# HeaderA.net
KiCad netlist of a schematic drawn in Altium Designer
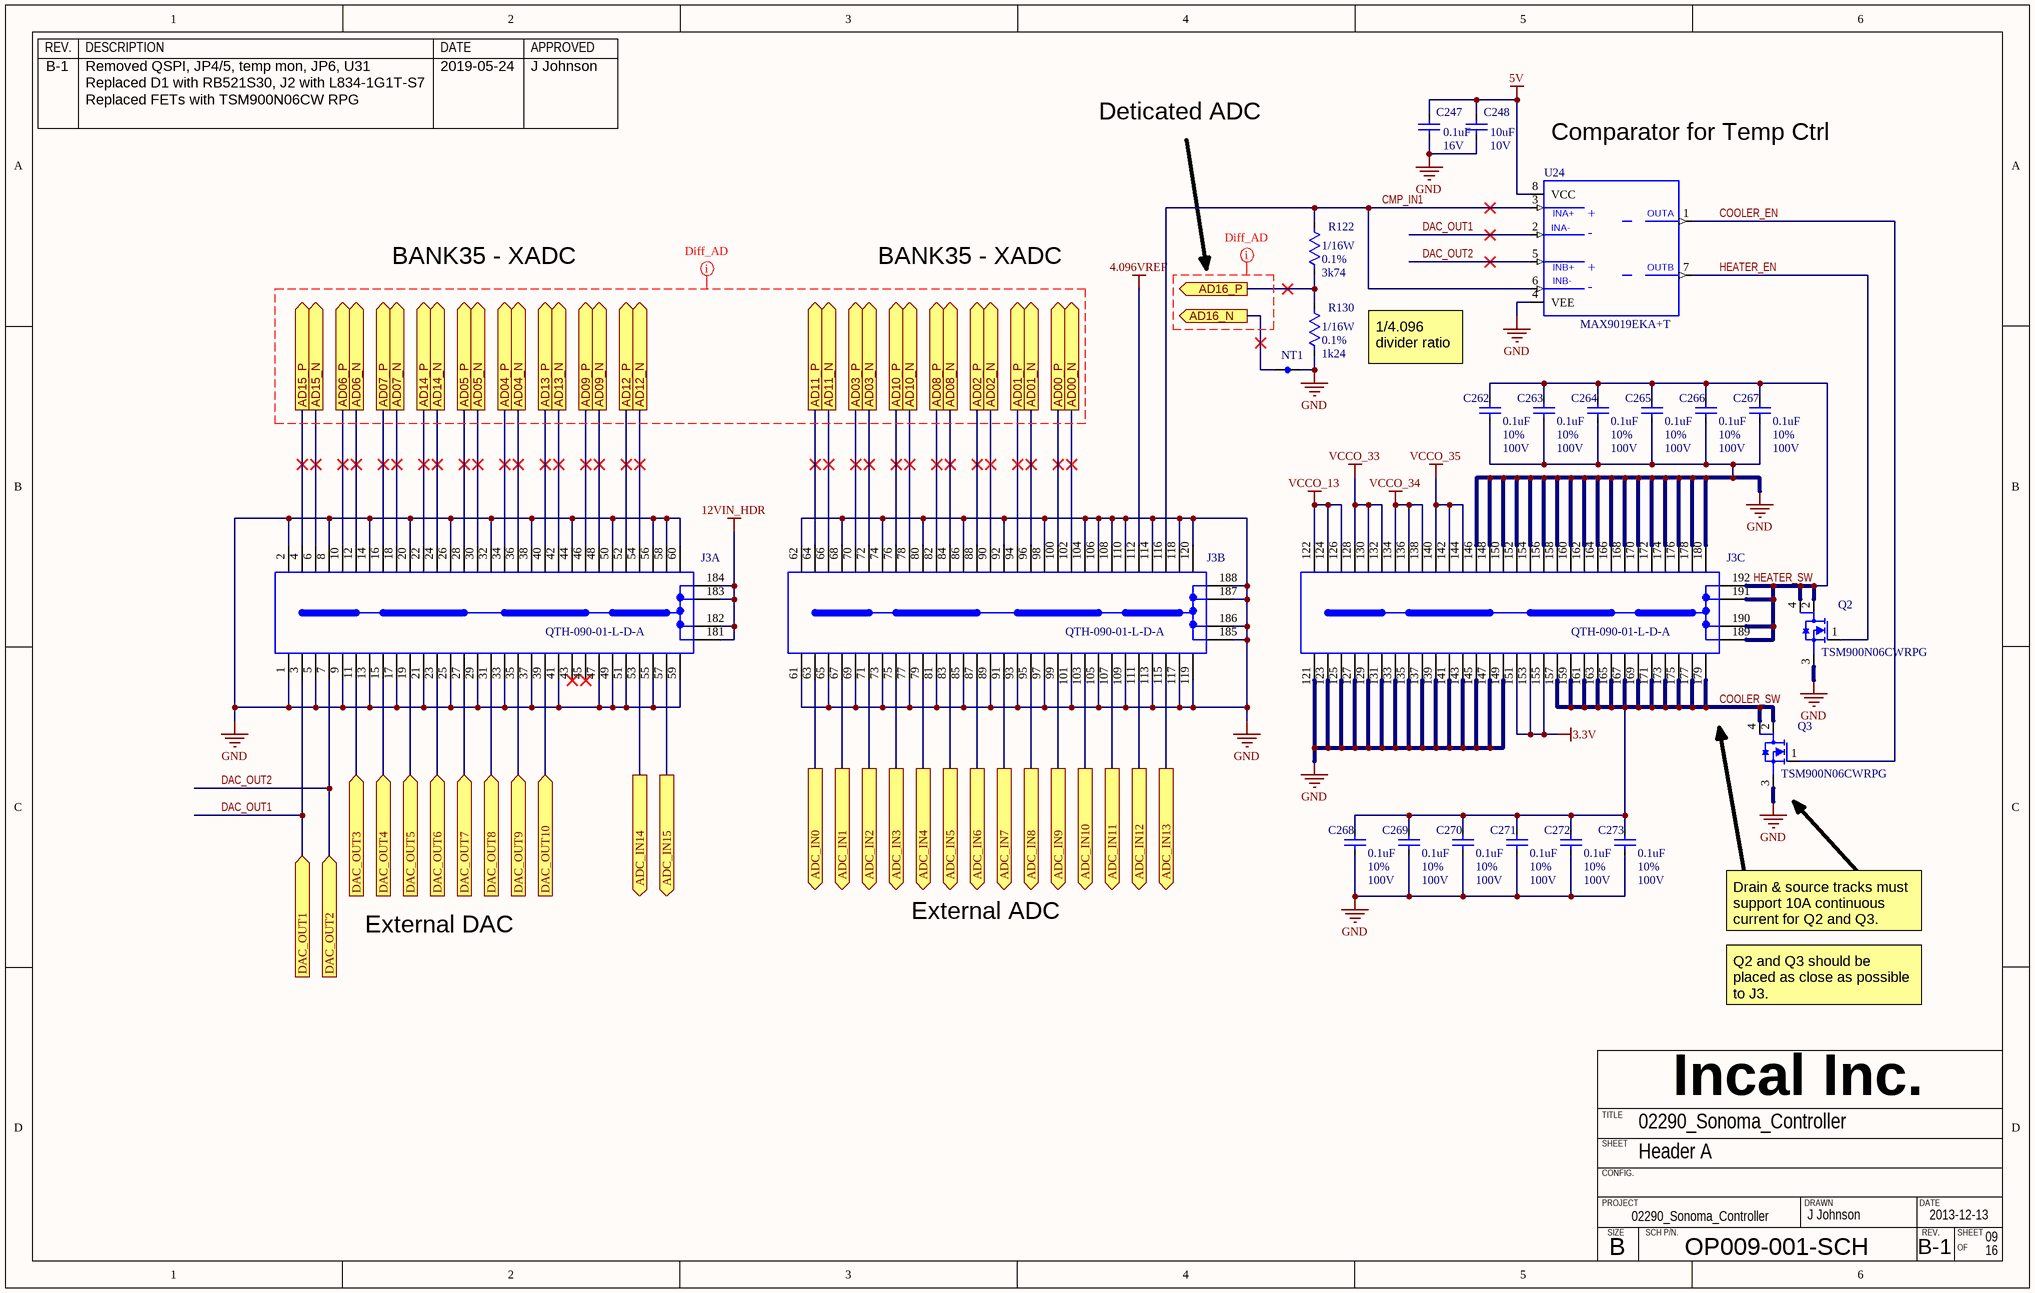
[diagram p0: HeaderA.SchDoc]

(export (version "E")
  (design (tool "Eeschema 10.0.6"))
  (components
    (comp (ref "C247")
      (value "0.1uF")
      (footprint "CAPC1005X33N")
      (description "Capacitor ceramic, X7R, 0.1uF, 16V, 10%, -55 to +125 C, EIA0402")
      (fields
        (field (name "TOLERANCE") "10%")
        (field (name "VOLTAGE") "16V")
        (field (name "Comment") "CAPACITOR_NP_TYPE1")
      )
      (libsource (lib "parts") (part "CAPACITOR_NP_TYPE1"))
    )
    (comp (ref "C248")
      (value "10uF")
      (footprint "CAPC1608X38N")
      (description "Capacitor ceramic, X5R, 10uF, 10V, 10%, -55 to +85 C, EIA0603")
      (fields
        (field (name "TOLERANCE") "10%")
        (field (name "VOLTAGE") "10V")
        (field (name "Comment") "CAPACITOR_NP_TYPE1")
      )
      (libsource (lib "parts") (part "CAPACITOR_NP_TYPE1"))
    )
    (comp (ref "C262")
      (value "0.1uF")
      (footprint "CAPC1608X38N")
      (description "Capacitor ceramic, X7R, 0.1uF, 100V, 10%, -55 to +125 C, EIA0603")
      (fields
        (field (name "TOLERANCE") "10%")
        (field (name "VOLTAGE") "100V")
        (field (name "Comment") "CAPACITOR_NP_TYPE1")
      )
      (libsource (lib "parts") (part "CAPACITOR_NP_TYPE1"))
    )
    (comp (ref "C263")
      (value "0.1uF")
      (footprint "CAPC1608X38N")
      (description "Capacitor ceramic, X7R, 0.1uF, 100V, 10%, -55 to +125 C, EIA0603")
      (fields
        (field (name "TOLERANCE") "10%")
        (field (name "VOLTAGE") "100V")
        (field (name "Comment") "CAPACITOR_NP_TYPE1")
      )
      (libsource (lib "parts") (part "CAPACITOR_NP_TYPE1"))
    )
    (comp (ref "C264")
      (value "0.1uF")
      (footprint "CAPC1608X38N")
      (description "Capacitor ceramic, X7R, 0.1uF, 100V, 10%, -55 to +125 C, EIA0603")
      (fields
        (field (name "TOLERANCE") "10%")
        (field (name "VOLTAGE") "100V")
        (field (name "Comment") "CAPACITOR_NP_TYPE1")
      )
      (libsource (lib "parts") (part "CAPACITOR_NP_TYPE1"))
    )
    (comp (ref "C265")
      (value "0.1uF")
      (footprint "CAPC1608X38N")
      (description "Capacitor ceramic, X7R, 0.1uF, 100V, 10%, -55 to +125 C, EIA0603")
      (fields
        (field (name "TOLERANCE") "10%")
        (field (name "VOLTAGE") "100V")
        (field (name "Comment") "CAPACITOR_NP_TYPE1")
      )
      (libsource (lib "parts") (part "CAPACITOR_NP_TYPE1"))
    )
    (comp (ref "C266")
      (value "0.1uF")
      (footprint "CAPC1608X38N")
      (description "Capacitor ceramic, X7R, 0.1uF, 100V, 10%, -55 to +125 C, EIA0603")
      (fields
        (field (name "TOLERANCE") "10%")
        (field (name "VOLTAGE") "100V")
        (field (name "Comment") "CAPACITOR_NP_TYPE1")
      )
      (libsource (lib "parts") (part "CAPACITOR_NP_TYPE1"))
    )
    (comp (ref "C267")
      (value "0.1uF")
      (footprint "CAPC1608X38N")
      (description "Capacitor ceramic, X7R, 0.1uF, 100V, 10%, -55 to +125 C, EIA0603")
      (fields
        (field (name "TOLERANCE") "10%")
        (field (name "VOLTAGE") "100V")
        (field (name "Comment") "CAPACITOR_NP_TYPE1")
      )
      (libsource (lib "parts") (part "CAPACITOR_NP_TYPE1"))
    )
    (comp (ref "C268")
      (value "0.1uF")
      (footprint "CAPC1608X38N")
      (description "Capacitor ceramic, X7R, 0.1uF, 100V, 10%, -55 to +125 C, EIA0603")
      (fields
        (field (name "TOLERANCE") "10%")
        (field (name "VOLTAGE") "100V")
        (field (name "Comment") "CAPACITOR_NP_TYPE1")
      )
      (libsource (lib "parts") (part "CAPACITOR_NP_TYPE1"))
    )
    (comp (ref "C269")
      (value "0.1uF")
      (footprint "CAPC1608X38N")
      (description "Capacitor ceramic, X7R, 0.1uF, 100V, 10%, -55 to +125 C, EIA0603")
      (fields
        (field (name "TOLERANCE") "10%")
        (field (name "VOLTAGE") "100V")
        (field (name "Comment") "CAPACITOR_NP_TYPE1")
      )
      (libsource (lib "parts") (part "CAPACITOR_NP_TYPE1"))
    )
    (comp (ref "C270")
      (value "0.1uF")
      (footprint "CAPC1608X38N")
      (description "Capacitor ceramic, X7R, 0.1uF, 100V, 10%, -55 to +125 C, EIA0603")
      (fields
        (field (name "TOLERANCE") "10%")
        (field (name "VOLTAGE") "100V")
        (field (name "Comment") "CAPACITOR_NP_TYPE1")
      )
      (libsource (lib "parts") (part "CAPACITOR_NP_TYPE1"))
    )
    (comp (ref "C271")
      (value "0.1uF")
      (footprint "CAPC1608X38N")
      (description "Capacitor ceramic, X7R, 0.1uF, 100V, 10%, -55 to +125 C, EIA0603")
      (fields
        (field (name "TOLERANCE") "10%")
        (field (name "VOLTAGE") "100V")
        (field (name "Comment") "CAPACITOR_NP_TYPE1")
      )
      (libsource (lib "parts") (part "CAPACITOR_NP_TYPE1"))
    )
    (comp (ref "C272")
      (value "0.1uF")
      (footprint "CAPC1608X38N")
      (description "Capacitor ceramic, X7R, 0.1uF, 100V, 10%, -55 to +125 C, EIA0603")
      (fields
        (field (name "TOLERANCE") "10%")
        (field (name "VOLTAGE") "100V")
        (field (name "Comment") "CAPACITOR_NP_TYPE1")
      )
      (libsource (lib "parts") (part "CAPACITOR_NP_TYPE1"))
    )
    (comp (ref "C273")
      (value "0.1uF")
      (footprint "CAPC1608X38N")
      (description "Capacitor ceramic, X7R, 0.1uF, 100V, 10%, -55 to +125 C, EIA0603")
      (fields
        (field (name "TOLERANCE") "10%")
        (field (name "VOLTAGE") "100V")
        (field (name "Comment") "CAPACITOR_NP_TYPE1")
      )
      (libsource (lib "parts") (part "CAPACITOR_NP_TYPE1"))
    )
    (comp (ref "J3")
      (value "QTH-090-01-L-D-A")
      (footprint "QTH-090-01-L-D-A")
      (description "Connector Header HS .5mm 180 pin DL AU")
      (libsource (lib "parts") (part "QTH-090-01-L-D-A"))
    )
    (comp (ref "NT1")
      (value "NET_TIE_1X1")
      (footprint "NET_TIE_1X1")
      (description "Net Tie 1 to 1")
      (libsource (lib "parts") (part "NET_TIE_1X1"))
    )
    (comp (ref "Q2")
      (value "TSM900N06CWRPG")
      (footprint "SOT230P700X180-4N")
      (description "Transistor MOSFET, N-Channel, 60V, 11A, 25W, SOT-223")
      (fields (field (name "POWER") "25W") (field (name "VOLTAGE") "60V"))
      (libsource (lib "parts") (part "TRANS_MOSFET_N-CH_TYPE4"))
    )
    (comp (ref "Q3")
      (value "TSM900N06CWRPG")
      (footprint "SOT230P700X180-4N")
      (description "Transistor MOSFET, N-Channel, 60V, 11A, 25W, SOT-223")
      (fields (field (name "POWER") "25W") (field (name "VOLTAGE") "60V"))
      (libsource (lib "parts") (part "TRANS_MOSFET_N-CH_TYPE4"))
    )
    (comp (ref "R122")
      (value "3k74")
      (footprint "RESC1005X33N")
      (description "Resistor, 3k74, 1/16W, 0.1%, -50 to +155 C, EIA0402, EIA(M)1005")
      (fields (field (name "VOLTAGE") "50V") (field (name "POWER") "1/16W") (field (name "TOLERANCE") "0.1%"))
      (libsource (lib "parts") (part "RESISTOR_TYPE1"))
    )
    (comp (ref "R130")
      (value "1k24")
      (footprint "RESC1005X33N")
      (description "Resistor, 1k24, 1/16W, 0.1%, -50 to +155 C, EIA0402, EIA(M)1005")
      (fields (field (name "VOLTAGE") "50V") (field (name "POWER") "1/16W") (field (name "TOLERANCE") "0.1%"))
      (libsource (lib "parts") (part "RESISTOR_TYPE1"))
    )
    (comp (ref "U24")
      (value "MAX9019EKA+T")
      (footprint "SOT65P280X145-8AN")
      (description "Comparator, Dual, Push-pull, 1.8V to 5.5V, 50mA, -40 to +85 C, , SOT-23-8")
      (fields (field (name "POWER") "Pow") (field (name "VOLTAGE") "1.8V to 5.5V"))
      (libsource (lib "parts") (part "MAX9019"))
    )
  )
  (nets
    (net (code "1") (name "/AD00_N") (class "Default")
      (node (ref "J3") (pin "102") (pinfunction "102_102") (pintype "passive"))
    )
    (net (code "2") (name "/AD00_P") (class "Default")
      (node (ref "J3") (pin "100") (pinfunction "100_100") (pintype "passive"))
    )
    (net (code "3") (name "/AD01_N") (class "Default")
      (node (ref "J3") (pin "96") (pinfunction "96_96") (pintype "passive"))
    )
    (net (code "4") (name "/AD01_P") (class "Default")
      (node (ref "J3") (pin "94") (pinfunction "94_94") (pintype "passive"))
    )
    (net (code "5") (name "/AD02_N") (class "Default")
      (node (ref "J3") (pin "90") (pinfunction "90_90") (pintype "passive"))
    )
    (net (code "6") (name "/AD02_P") (class "Default")
      (node (ref "J3") (pin "88") (pinfunction "88_88") (pintype "passive"))
    )
    (net (code "7") (name "/AD03_N") (class "Default")
      (node (ref "J3") (pin "72") (pinfunction "72_72") (pintype "passive"))
    )
    (net (code "8") (name "/AD03_P") (class "Default")
      (node (ref "J3") (pin "70") (pinfunction "70_70") (pintype "passive"))
    )
    (net (code "9") (name "/AD04_N") (class "Default")
      (node (ref "J3") (pin "36") (pinfunction "36_36") (pintype "passive"))
    )
    (net (code "10") (name "/AD04_P") (class "Default")
      (node (ref "J3") (pin "34") (pinfunction "34_34") (pintype "passive"))
    )
    (net (code "11") (name "/AD05_N") (class "Default")
      (node (ref "J3") (pin "30") (pinfunction "30_30") (pintype "passive"))
    )
    (net (code "12") (name "/AD05_P") (class "Default")
      (node (ref "J3") (pin "28") (pinfunction "28_28") (pintype "passive"))
    )
    (net (code "13") (name "/AD06_N") (class "Default")
      (node (ref "J3") (pin "12") (pinfunction "12_12") (pintype "passive"))
    )
    (net (code "14") (name "/AD06_P") (class "Default")
      (node (ref "J3") (pin "10") (pinfunction "10_10") (pintype "passive"))
    )
    (net (code "15") (name "/AD07_N") (class "Default")
      (node (ref "J3") (pin "18") (pinfunction "18_18") (pintype "passive"))
    )
    (net (code "16") (name "/AD07_P") (class "Default")
      (node (ref "J3") (pin "16") (pinfunction "16_16") (pintype "passive"))
    )
    (net (code "17") (name "/AD08_N") (class "Default")
      (node (ref "J3") (pin "84") (pinfunction "84_84") (pintype "passive"))
    )
    (net (code "18") (name "/AD08_P") (class "Default")
      (node (ref "J3") (pin "82") (pinfunction "82_82") (pintype "passive"))
    )
    (net (code "19") (name "/AD09_N") (class "Default")
      (node (ref "J3") (pin "48") (pinfunction "48_48") (pintype "passive"))
    )
    (net (code "20") (name "/AD09_P") (class "Default")
      (node (ref "J3") (pin "46") (pinfunction "46_46") (pintype "passive"))
    )
    (net (code "21") (name "/AD10_N") (class "Default")
      (node (ref "J3") (pin "78") (pinfunction "78_78") (pintype "passive"))
    )
    (net (code "22") (name "/AD10_P") (class "Default")
      (node (ref "J3") (pin "76") (pinfunction "76_76") (pintype "passive"))
    )
    (net (code "23") (name "/AD11_N") (class "Default")
      (node (ref "J3") (pin "66") (pinfunction "66_66") (pintype "passive"))
    )
    (net (code "24") (name "/AD11_P") (class "Default")
      (node (ref "J3") (pin "64") (pinfunction "64_64") (pintype "passive"))
    )
    (net (code "25") (name "/AD12_N") (class "Default")
      (node (ref "J3") (pin "54") (pinfunction "54_54") (pintype "passive"))
    )
    (net (code "26") (name "/AD12_P") (class "Default")
      (node (ref "J3") (pin "52") (pinfunction "52_52") (pintype "passive"))
    )
    (net (code "27") (name "/AD13_N") (class "Default")
      (node (ref "J3") (pin "42") (pinfunction "42_42") (pintype "passive"))
    )
    (net (code "28") (name "/AD13_P") (class "Default")
      (node (ref "J3") (pin "40") (pinfunction "40_40") (pintype "passive"))
    )
    (net (code "29") (name "/AD14_N") (class "Default")
      (node (ref "J3") (pin "24") (pinfunction "24_24") (pintype "passive"))
    )
    (net (code "30") (name "/AD14_P") (class "Default")
      (node (ref "J3") (pin "22") (pinfunction "22_22") (pintype "passive"))
    )
    (net (code "31") (name "/AD15_N") (class "Default")
      (node (ref "J3") (pin "6") (pinfunction "6_6") (pintype "passive"))
    )
    (net (code "32") (name "/AD15_P") (class "Default")
      (node (ref "J3") (pin "4") (pinfunction "4_4") (pintype "passive"))
    )
    (net (code "33") (name "/AD16_N") (class "Default")
      (node (ref "NT1") (pin "1") (pinfunction "1_1") (pintype "passive"))
    )
    (net (code "34") (name "/AD16_P") (class "Default")
      (node (ref "R122") (pin "2") (pinfunction "2_2") (pintype "passive"))
      (node (ref "R130") (pin "1") (pinfunction "1_1") (pintype "passive"))
    )
    (net (code "35") (name "/ADC_IN0") (class "Default")
      (node (ref "J3") (pin "63") (pinfunction "63_63") (pintype "passive"))
    )
    (net (code "36") (name "/ADC_IN1") (class "Default")
      (node (ref "J3") (pin "67") (pinfunction "67_67") (pintype "passive"))
    )
    (net (code "37") (name "/ADC_IN2") (class "Default")
      (node (ref "J3") (pin "71") (pinfunction "71_71") (pintype "passive"))
    )
    (net (code "38") (name "/ADC_IN3") (class "Default")
      (node (ref "J3") (pin "75") (pinfunction "75_75") (pintype "passive"))
    )
    (net (code "39") (name "/ADC_IN4") (class "Default")
      (node (ref "J3") (pin "79") (pinfunction "79_79") (pintype "passive"))
    )
    (net (code "40") (name "/ADC_IN5") (class "Default")
      (node (ref "J3") (pin "83") (pinfunction "83_83") (pintype "passive"))
    )
    (net (code "41") (name "/ADC_IN6") (class "Default")
      (node (ref "J3") (pin "87") (pinfunction "87_87") (pintype "passive"))
    )
    (net (code "42") (name "/ADC_IN7") (class "Default")
      (node (ref "J3") (pin "91") (pinfunction "91_91") (pintype "passive"))
    )
    (net (code "43") (name "/ADC_IN8") (class "Default")
      (node (ref "J3") (pin "95") (pinfunction "95_95") (pintype "passive"))
    )
    (net (code "44") (name "/ADC_IN9") (class "Default")
      (node (ref "J3") (pin "99") (pinfunction "99_99") (pintype "passive"))
    )
    (net (code "45") (name "/ADC_IN10") (class "Default")
      (node (ref "J3") (pin "103") (pinfunction "103_103") (pintype "passive"))
    )
    (net (code "46") (name "/ADC_IN11") (class "Default")
      (node (ref "J3") (pin "107") (pinfunction "107_107") (pintype "passive"))
    )
    (net (code "47") (name "/ADC_IN12") (class "Default")
      (node (ref "J3") (pin "111") (pinfunction "111_111") (pintype "passive"))
    )
    (net (code "48") (name "/ADC_IN13") (class "Default")
      (node (ref "J3") (pin "115") (pinfunction "115_115") (pintype "passive"))
    )
    (net (code "49") (name "/ADC_IN14") (class "Default")
      (node (ref "J3") (pin "53") (pinfunction "53_53") (pintype "passive"))
    )
    (net (code "50") (name "/ADC_IN15") (class "Default")
      (node (ref "J3") (pin "57") (pinfunction "57_57") (pintype "passive"))
    )
    (net (code "51") (name "/CMP_IN1") (class "Default")
      (node (ref "J3") (pin "116") (pinfunction "116_116") (pintype "passive"))
      (node (ref "R122") (pin "1") (pinfunction "1_1") (pintype "passive"))
      (node (ref "U24") (pin "3") (pinfunction "INA+_3") (pintype "input"))
      (node (ref "U24") (pin "6") (pinfunction "INB-_6") (pintype "input"))
    )
    (net (code "52") (name "/COOLER_EN") (class "Default")
      (node (ref "Q3") (pin "1") (pinfunction "G_1") (pintype "passive"))
      (node (ref "U24") (pin "1") (pinfunction "OUTA_1") (pintype "output"))
    )
    (net (code "53") (name "/COOLER_SW") (class "Default")
      (node (ref "C268") (pin "1") (pinfunction "1_1") (pintype "passive"))
      (node (ref "C269") (pin "1") (pinfunction "1_1") (pintype "passive"))
      (node (ref "C270") (pin "1") (pinfunction "1_1") (pintype "passive"))
      (node (ref "C271") (pin "1") (pinfunction "1_1") (pintype "passive"))
      (node (ref "C272") (pin "1") (pinfunction "1_1") (pintype "passive"))
      (node (ref "C273") (pin "1") (pinfunction "1_1") (pintype "passive"))
      (node (ref "J3") (pin "157") (pinfunction "157_157") (pintype "passive"))
      (node (ref "J3") (pin "159") (pinfunction "159_159") (pintype "passive"))
      (node (ref "J3") (pin "161") (pinfunction "161_161") (pintype "passive"))
      (node (ref "J3") (pin "163") (pinfunction "163_163") (pintype "passive"))
      (node (ref "J3") (pin "165") (pinfunction "165_165") (pintype "passive"))
      (node (ref "J3") (pin "167") (pinfunction "167_167") (pintype "passive"))
      (node (ref "J3") (pin "169") (pinfunction "169_169") (pintype "passive"))
      (node (ref "J3") (pin "171") (pinfunction "171_171") (pintype "passive"))
      (node (ref "J3") (pin "173") (pinfunction "173_173") (pintype "passive"))
      (node (ref "J3") (pin "175") (pinfunction "175_175") (pintype "passive"))
      (node (ref "J3") (pin "177") (pinfunction "177_177") (pintype "passive"))
      (node (ref "J3") (pin "179") (pinfunction "179_179") (pintype "passive"))
      (node (ref "Q3") (pin "2") (pinfunction "D_2") (pintype "passive"))
      (node (ref "Q3") (pin "4") (pinfunction "D_4") (pintype "passive"))
    )
    (net (code "54") (name "/DAC_OUT1") (class "Default")
      (node (ref "J3") (pin "3") (pinfunction "3_3") (pintype "passive"))
      (node (ref "U24") (pin "2") (pinfunction "INA-_2") (pintype "input"))
    )
    (net (code "55") (name "/DAC_OUT2") (class "Default")
      (node (ref "J3") (pin "7") (pinfunction "7_7") (pintype "passive"))
      (node (ref "U24") (pin "5") (pinfunction "INB+_5") (pintype "input"))
    )
    (net (code "56") (name "/DAC_OUT3") (class "Default")
      (node (ref "J3") (pin "11") (pinfunction "11_11") (pintype "passive"))
    )
    (net (code "57") (name "/DAC_OUT4") (class "Default")
      (node (ref "J3") (pin "15") (pinfunction "15_15") (pintype "passive"))
    )
    (net (code "58") (name "/DAC_OUT5") (class "Default")
      (node (ref "J3") (pin "19") (pinfunction "19_19") (pintype "passive"))
    )
    (net (code "59") (name "/DAC_OUT6") (class "Default")
      (node (ref "J3") (pin "23") (pinfunction "23_23") (pintype "passive"))
    )
    (net (code "60") (name "/DAC_OUT7") (class "Default")
      (node (ref "J3") (pin "27") (pinfunction "27_27") (pintype "passive"))
    )
    (net (code "61") (name "/DAC_OUT8") (class "Default")
      (node (ref "J3") (pin "31") (pinfunction "31_31") (pintype "passive"))
    )
    (net (code "62") (name "/DAC_OUT9") (class "Default")
      (node (ref "J3") (pin "35") (pinfunction "35_35") (pintype "passive"))
    )
    (net (code "63") (name "/DAC_OUT10") (class "Default")
      (node (ref "J3") (pin "39") (pinfunction "39_39") (pintype "passive"))
    )
    (net (code "64") (name "/HEATER_EN") (class "Default")
      (node (ref "Q2") (pin "1") (pinfunction "G_1") (pintype "passive"))
      (node (ref "U24") (pin "7") (pinfunction "OUTB_7") (pintype "output"))
    )
    (net (code "65") (name "/HEATER_SW") (class "Default")
      (node (ref "C262") (pin "1") (pinfunction "1_1") (pintype "passive"))
      (node (ref "C263") (pin "1") (pinfunction "1_1") (pintype "passive"))
      (node (ref "C264") (pin "1") (pinfunction "1_1") (pintype "passive"))
      (node (ref "C265") (pin "1") (pinfunction "1_1") (pintype "passive"))
      (node (ref "C266") (pin "1") (pinfunction "1_1") (pintype "passive"))
      (node (ref "C267") (pin "1") (pinfunction "1_1") (pintype "passive"))
      (node (ref "J3") (pin "189") (pinfunction "189_189") (pintype "passive"))
      (node (ref "J3") (pin "190") (pinfunction "190_190") (pintype "passive"))
      (node (ref "J3") (pin "191") (pinfunction "191_191") (pintype "passive"))
      (node (ref "J3") (pin "192") (pinfunction "192_192") (pintype "passive"))
      (node (ref "Q2") (pin "2") (pinfunction "D_2") (pintype "passive"))
      (node (ref "Q2") (pin "4") (pinfunction "D_4") (pintype "passive"))
    )
    (net (code "66") (name "3.3V") (class "Default")
      (node (ref "J3") (pin "151") (pinfunction "151_151") (pintype "passive"))
      (node (ref "J3") (pin "153") (pinfunction "153_153") (pintype "passive"))
      (node (ref "J3") (pin "155") (pinfunction "155_155") (pintype "passive"))
    )
    (net (code "67") (name "4.096VREF") (class "Default")
      (node (ref "J3") (pin "112") (pinfunction "112_112") (pintype "passive"))
    )
    (net (code "68") (name "5V") (class "Default")
      (node (ref "C247") (pin "1") (pinfunction "1_1") (pintype "passive"))
      (node (ref "C248") (pin "1") (pinfunction "1_1") (pintype "passive"))
      (node (ref "U24") (pin "8") (pinfunction "VCC_8") (pintype "power_in"))
    )
    (net (code "69") (name "12VIN_HDR") (class "Default")
      (node (ref "J3") (pin "181") (pinfunction "181_181") (pintype "passive"))
      (node (ref "J3") (pin "182") (pinfunction "182_182") (pintype "passive"))
      (node (ref "J3") (pin "183") (pinfunction "183_183") (pintype "passive"))
      (node (ref "J3") (pin "184") (pinfunction "184_184") (pintype "passive"))
    )
    (net (code "70") (name "GND") (class "Default")
      (node (ref "C247") (pin "2") (pinfunction "2_2") (pintype "passive"))
      (node (ref "C248") (pin "2") (pinfunction "2_2") (pintype "passive"))
      (node (ref "C262") (pin "2") (pinfunction "2_2") (pintype "passive"))
      (node (ref "C263") (pin "2") (pinfunction "2_2") (pintype "passive"))
      (node (ref "C264") (pin "2") (pinfunction "2_2") (pintype "passive"))
      (node (ref "C265") (pin "2") (pinfunction "2_2") (pintype "passive"))
      (node (ref "C266") (pin "2") (pinfunction "2_2") (pintype "passive"))
      (node (ref "C267") (pin "2") (pinfunction "2_2") (pintype "passive"))
      (node (ref "C268") (pin "2") (pinfunction "2_2") (pintype "passive"))
      (node (ref "C269") (pin "2") (pinfunction "2_2") (pintype "passive"))
      (node (ref "C270") (pin "2") (pinfunction "2_2") (pintype "passive"))
      (node (ref "C271") (pin "2") (pinfunction "2_2") (pintype "passive"))
      (node (ref "C272") (pin "2") (pinfunction "2_2") (pintype "passive"))
      (node (ref "C273") (pin "2") (pinfunction "2_2") (pintype "passive"))
      (node (ref "J3") (pin "1") (pinfunction "1_1") (pintype "passive"))
      (node (ref "J3") (pin "101") (pinfunction "101_101") (pintype "passive"))
      (node (ref "J3") (pin "104") (pinfunction "104_104") (pintype "passive"))
      (node (ref "J3") (pin "105") (pinfunction "105_105") (pintype "passive"))
      (node (ref "J3") (pin "106") (pinfunction "106_106") (pintype "passive"))
      (node (ref "J3") (pin "108") (pinfunction "108_108") (pintype "passive"))
      (node (ref "J3") (pin "109") (pinfunction "109_109") (pintype "passive"))
      (node (ref "J3") (pin "110") (pinfunction "110_110") (pintype "passive"))
      (node (ref "J3") (pin "113") (pinfunction "113_113") (pintype "passive"))
      (node (ref "J3") (pin "114") (pinfunction "114_114") (pintype "passive"))
      (node (ref "J3") (pin "117") (pinfunction "117_117") (pintype "passive"))
      (node (ref "J3") (pin "118") (pinfunction "118_118") (pintype "passive"))
      (node (ref "J3") (pin "119") (pinfunction "119_119") (pintype "passive"))
      (node (ref "J3") (pin "120") (pinfunction "120_120") (pintype "passive"))
      (node (ref "J3") (pin "121") (pinfunction "121_121") (pintype "passive"))
      (node (ref "J3") (pin "123") (pinfunction "123_123") (pintype "passive"))
      (node (ref "J3") (pin "125") (pinfunction "125_125") (pintype "passive"))
      (node (ref "J3") (pin "127") (pinfunction "127_127") (pintype "passive"))
      (node (ref "J3") (pin "129") (pinfunction "129_129") (pintype "passive"))
      (node (ref "J3") (pin "13") (pinfunction "13_13") (pintype "passive"))
      (node (ref "J3") (pin "131") (pinfunction "131_131") (pintype "passive"))
      (node (ref "J3") (pin "133") (pinfunction "133_133") (pintype "passive"))
      (node (ref "J3") (pin "135") (pinfunction "135_135") (pintype "passive"))
      (node (ref "J3") (pin "137") (pinfunction "137_137") (pintype "passive"))
      (node (ref "J3") (pin "139") (pinfunction "139_139") (pintype "passive"))
      (node (ref "J3") (pin "14") (pinfunction "14_14") (pintype "passive"))
      (node (ref "J3") (pin "141") (pinfunction "141_141") (pintype "passive"))
      (node (ref "J3") (pin "143") (pinfunction "143_143") (pintype "passive"))
      (node (ref "J3") (pin "145") (pinfunction "145_145") (pintype "passive"))
      (node (ref "J3") (pin "146") (pinfunction "146_146") (pintype "passive"))
      (node (ref "J3") (pin "147") (pinfunction "147_147") (pintype "passive"))
      (node (ref "J3") (pin "148") (pinfunction "148_148") (pintype "passive"))
      (node (ref "J3") (pin "149") (pinfunction "149_149") (pintype "passive"))
      (node (ref "J3") (pin "150") (pinfunction "150_150") (pintype "passive"))
      (node (ref "J3") (pin "152") (pinfunction "152_152") (pintype "passive"))
      (node (ref "J3") (pin "154") (pinfunction "154_154") (pintype "passive"))
      (node (ref "J3") (pin "156") (pinfunction "156_156") (pintype "passive"))
      (node (ref "J3") (pin "158") (pinfunction "158_158") (pintype "passive"))
      (node (ref "J3") (pin "160") (pinfunction "160_160") (pintype "passive"))
      (node (ref "J3") (pin "162") (pinfunction "162_162") (pintype "passive"))
      (node (ref "J3") (pin "164") (pinfunction "164_164") (pintype "passive"))
      (node (ref "J3") (pin "166") (pinfunction "166_166") (pintype "passive"))
      (node (ref "J3") (pin "168") (pinfunction "168_168") (pintype "passive"))
      (node (ref "J3") (pin "17") (pinfunction "17_17") (pintype "passive"))
      (node (ref "J3") (pin "170") (pinfunction "170_170") (pintype "passive"))
      (node (ref "J3") (pin "172") (pinfunction "172_172") (pintype "passive"))
      (node (ref "J3") (pin "174") (pinfunction "174_174") (pintype "passive"))
      (node (ref "J3") (pin "176") (pinfunction "176_176") (pintype "passive"))
      (node (ref "J3") (pin "178") (pinfunction "178_178") (pintype "passive"))
      (node (ref "J3") (pin "180") (pinfunction "180_180") (pintype "passive"))
      (node (ref "J3") (pin "185") (pinfunction "185_185") (pintype "passive"))
      (node (ref "J3") (pin "186") (pinfunction "186_186") (pintype "passive"))
      (node (ref "J3") (pin "187") (pinfunction "187_187") (pintype "passive"))
      (node (ref "J3") (pin "188") (pinfunction "188_188") (pintype "passive"))
      (node (ref "J3") (pin "2") (pinfunction "2_2") (pintype "passive"))
      (node (ref "J3") (pin "20") (pinfunction "20_20") (pintype "passive"))
      (node (ref "J3") (pin "21") (pinfunction "21_21") (pintype "passive"))
      (node (ref "J3") (pin "25") (pinfunction "25_25") (pintype "passive"))
      (node (ref "J3") (pin "26") (pinfunction "26_26") (pintype "passive"))
      (node (ref "J3") (pin "29") (pinfunction "29_29") (pintype "passive"))
      (node (ref "J3") (pin "32") (pinfunction "32_32") (pintype "passive"))
      (node (ref "J3") (pin "33") (pinfunction "33_33") (pintype "passive"))
      (node (ref "J3") (pin "37") (pinfunction "37_37") (pintype "passive"))
      (node (ref "J3") (pin "38") (pinfunction "38_38") (pintype "passive"))
      (node (ref "J3") (pin "41") (pinfunction "41_41") (pintype "passive"))
      (node (ref "J3") (pin "44") (pinfunction "44_44") (pintype "passive"))
      (node (ref "J3") (pin "47") (pinfunction "47_47") (pintype "passive"))
      (node (ref "J3") (pin "49") (pinfunction "49_49") (pintype "passive"))
      (node (ref "J3") (pin "5") (pinfunction "5_5") (pintype "passive"))
      (node (ref "J3") (pin "50") (pinfunction "50_50") (pintype "passive"))
      (node (ref "J3") (pin "51") (pinfunction "51_51") (pintype "passive"))
      (node (ref "J3") (pin "55") (pinfunction "55_55") (pintype "passive"))
      (node (ref "J3") (pin "56") (pinfunction "56_56") (pintype "passive"))
      (node (ref "J3") (pin "58") (pinfunction "58_58") (pintype "passive"))
      (node (ref "J3") (pin "59") (pinfunction "59_59") (pintype "passive"))
      (node (ref "J3") (pin "60") (pinfunction "60_60") (pintype "passive"))
      (node (ref "J3") (pin "61") (pinfunction "61_61") (pintype "passive"))
      (node (ref "J3") (pin "62") (pinfunction "62_62") (pintype "passive"))
      (node (ref "J3") (pin "65") (pinfunction "65_65") (pintype "passive"))
      (node (ref "J3") (pin "68") (pinfunction "68_68") (pintype "passive"))
      (node (ref "J3") (pin "69") (pinfunction "69_69") (pintype "passive"))
      (node (ref "J3") (pin "73") (pinfunction "73_73") (pintype "passive"))
      (node (ref "J3") (pin "74") (pinfunction "74_74") (pintype "passive"))
      (node (ref "J3") (pin "77") (pinfunction "77_77") (pintype "passive"))
      (node (ref "J3") (pin "8") (pinfunction "8_8") (pintype "passive"))
      (node (ref "J3") (pin "80") (pinfunction "80_80") (pintype "passive"))
      (node (ref "J3") (pin "81") (pinfunction "81_81") (pintype "passive"))
      (node (ref "J3") (pin "85") (pinfunction "85_85") (pintype "passive"))
      (node (ref "J3") (pin "86") (pinfunction "86_86") (pintype "passive"))
      (node (ref "J3") (pin "89") (pinfunction "89_89") (pintype "passive"))
      (node (ref "J3") (pin "9") (pinfunction "9_9") (pintype "passive"))
      (node (ref "J3") (pin "92") (pinfunction "92_92") (pintype "passive"))
      (node (ref "J3") (pin "93") (pinfunction "93_93") (pintype "passive"))
      (node (ref "J3") (pin "97") (pinfunction "97_97") (pintype "passive"))
      (node (ref "J3") (pin "98") (pinfunction "98_98") (pintype "passive"))
      (node (ref "NT1") (pin "2") (pinfunction "2_2") (pintype "passive"))
      (node (ref "Q2") (pin "3") (pinfunction "S_3") (pintype "passive"))
      (node (ref "Q3") (pin "3") (pinfunction "S_3") (pintype "passive"))
      (node (ref "R130") (pin "2") (pinfunction "2_2") (pintype "passive"))
      (node (ref "U24") (pin "4") (pinfunction "VEE_4") (pintype "power_in"))
    )
    (net (code "71") (name "VCCO_13") (class "Default")
      (node (ref "J3") (pin "122") (pinfunction "122_122") (pintype "passive"))
      (node (ref "J3") (pin "124") (pinfunction "124_124") (pintype "passive"))
      (node (ref "J3") (pin "126") (pinfunction "126_126") (pintype "passive"))
    )
    (net (code "72") (name "VCCO_33") (class "Default")
      (node (ref "J3") (pin "128") (pinfunction "128_128") (pintype "passive"))
      (node (ref "J3") (pin "130") (pinfunction "130_130") (pintype "passive"))
      (node (ref "J3") (pin "132") (pinfunction "132_132") (pintype "passive"))
    )
    (net (code "73") (name "VCCO_34") (class "Default")
      (node (ref "J3") (pin "134") (pinfunction "134_134") (pintype "passive"))
      (node (ref "J3") (pin "136") (pinfunction "136_136") (pintype "passive"))
      (node (ref "J3") (pin "138") (pinfunction "138_138") (pintype "passive"))
    )
    (net (code "74") (name "VCCO_35") (class "Default")
      (node (ref "J3") (pin "140") (pinfunction "140_140") (pintype "passive"))
      (node (ref "J3") (pin "142") (pinfunction "142_142") (pintype "passive"))
      (node (ref "J3") (pin "144") (pinfunction "144_144") (pintype "passive"))
    )
    (net (code "75") (name "unconnected-(J3-Pad43)") (class "Default")
      (node (ref "J3") (pin "43") (pinfunction "43_43") (pintype "passive+no_connect"))
    )
    (net (code "76") (name "unconnected-(J3-Pad45)") (class "Default")
      (node (ref "J3") (pin "45") (pinfunction "45_45") (pintype "passive+no_connect"))
    )
  )
)
